# schdesign.net
KiCad netlist of a schematic drawn in EasyEDA
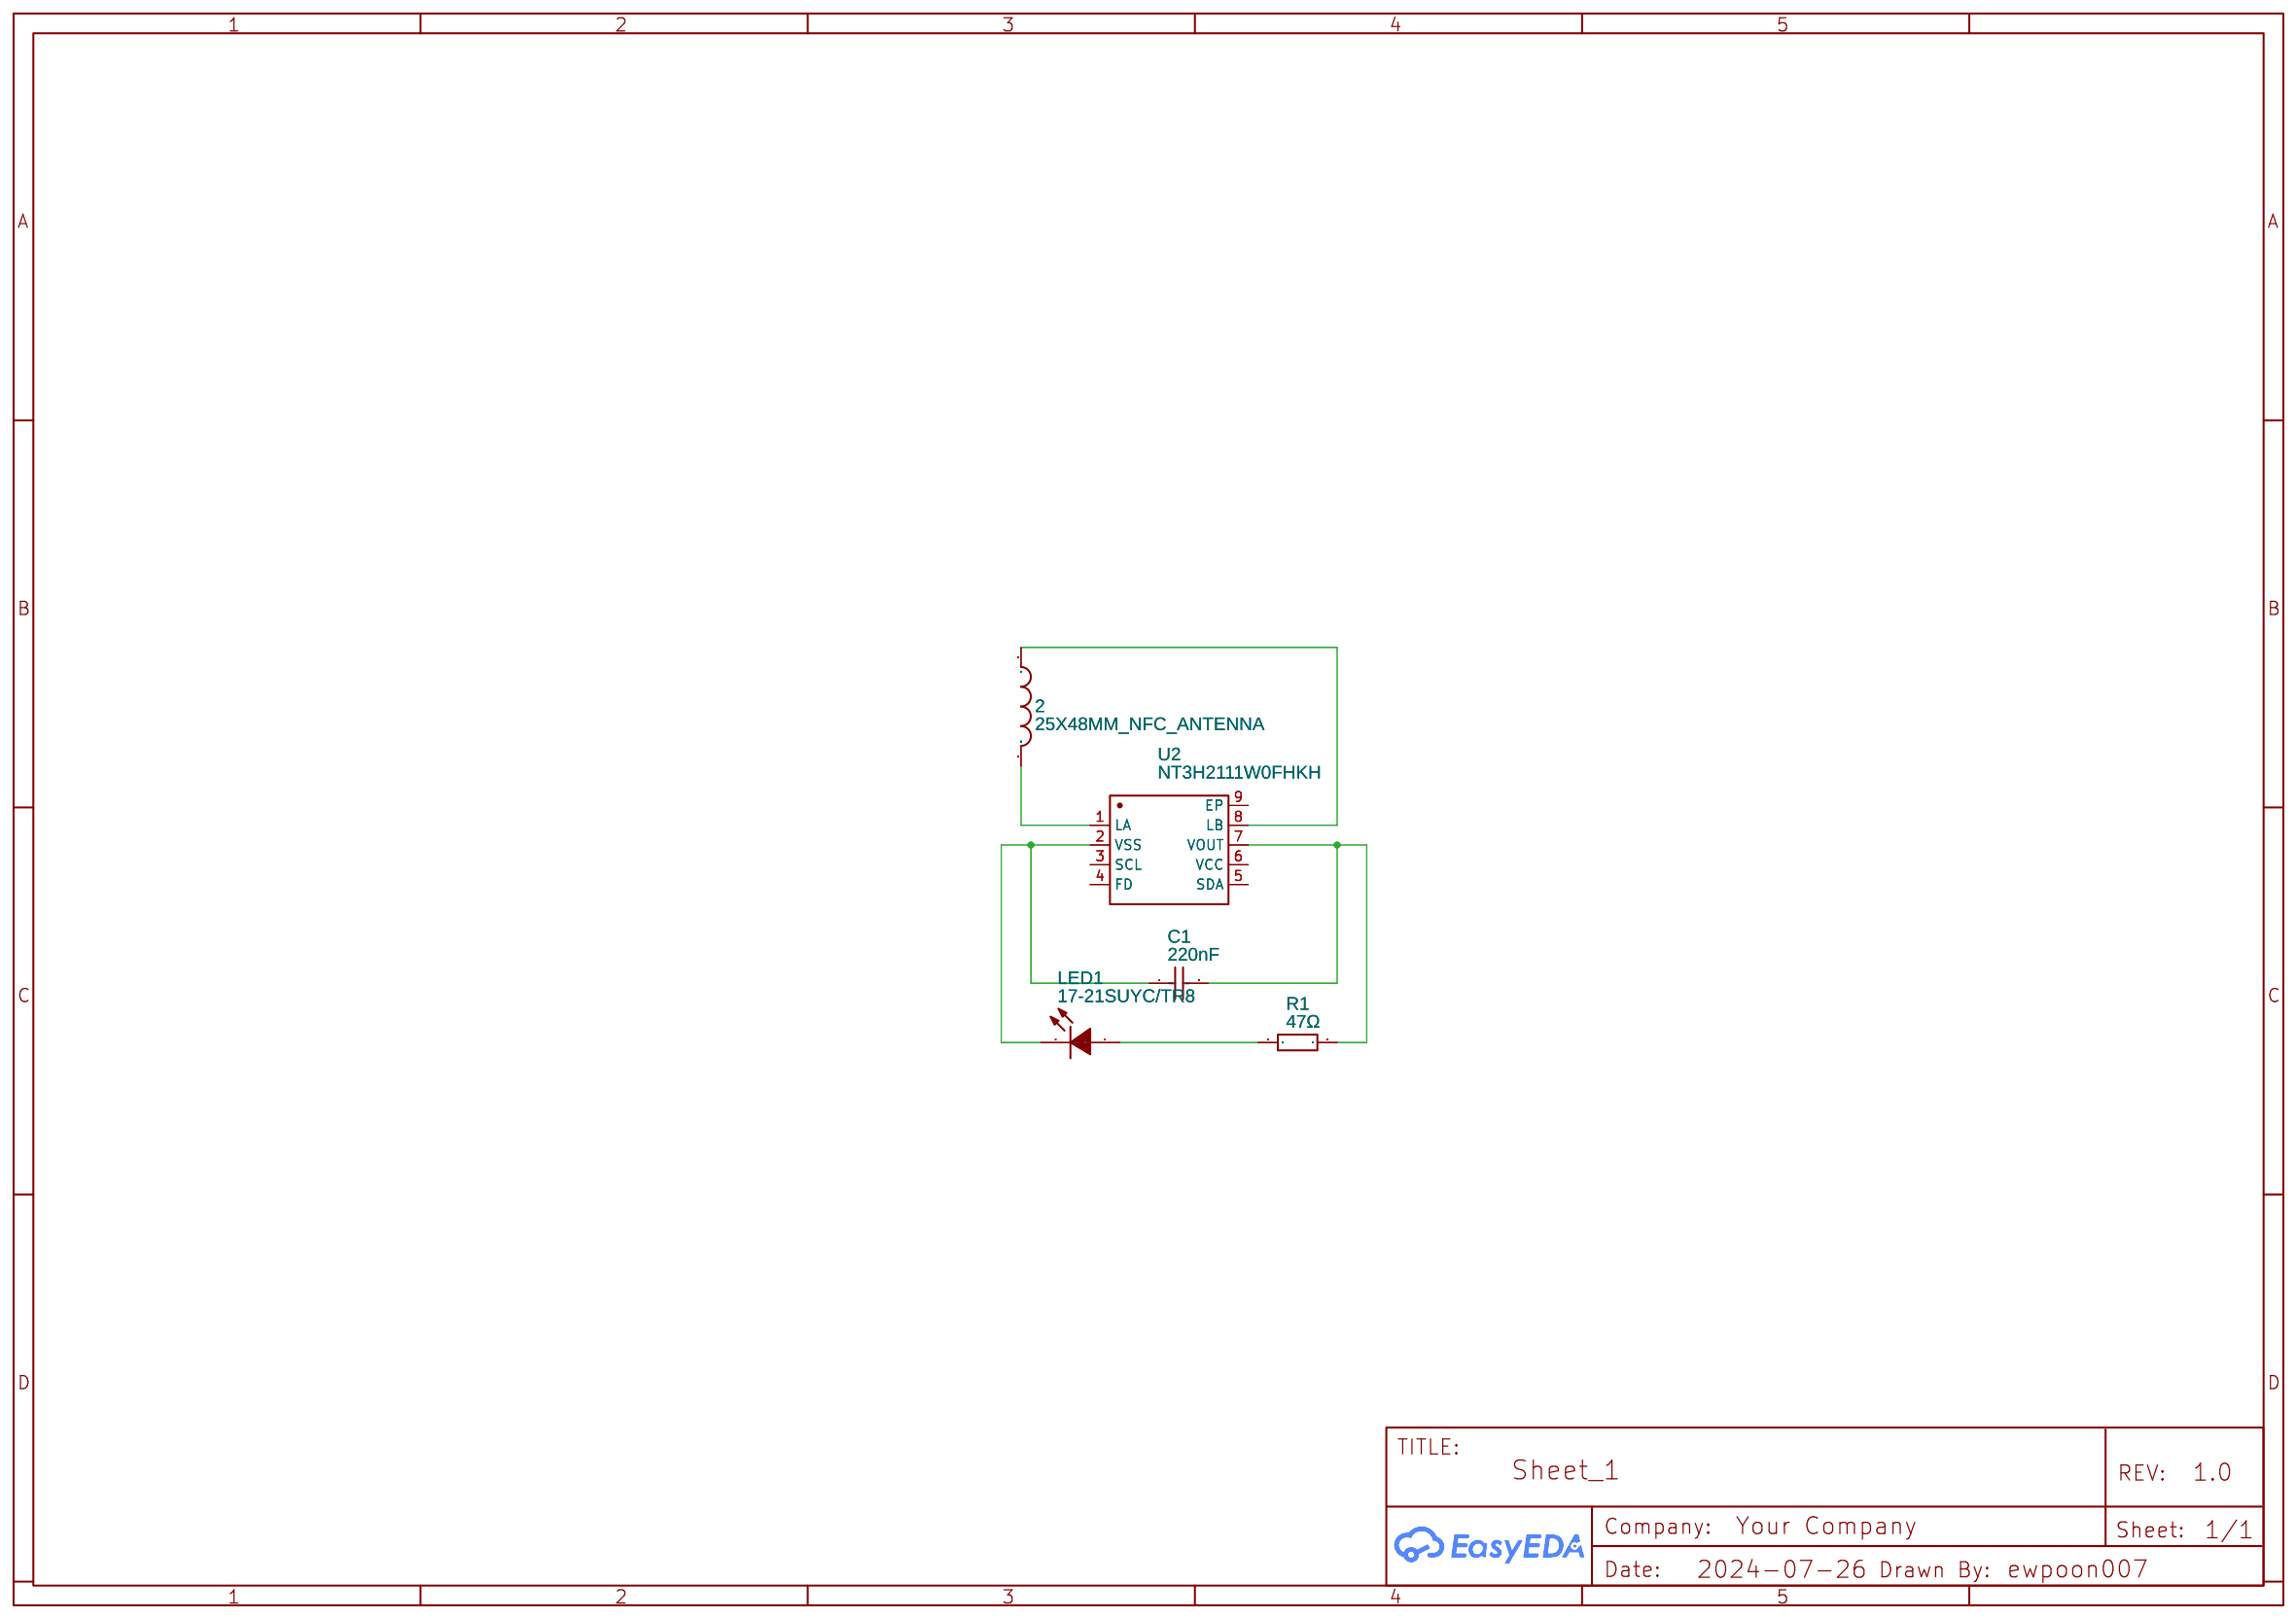
[diagram p0: schematic sheet]

(export (version "E")
  (design (tool "Eeschema 10.0.6"))
  (components
    (comp (ref "2") (value "25X48MM_NFC_ANTENNA") (libsource (lib "") (part "25X48MM_NFC_ANTENNA")))
    (comp (ref "C1")
      (value "220nF")
      (fields
        (field (name "Manufacturer Part") "CL10B224KA8NNNC")
        (field (name "Manufacturer") "SAMSUNG(三星)")
      )
      (libsource (lib "") (part "CL10B224KA8NNNC"))
    )
    (comp (ref "LED1")
      (value "17-21SUYC/TR8")
      (fields (field (name "Manufacturer Part") "KT-0805黄灯") (field (name "Manufacturer") "KENTO"))
      (libsource (lib "") (part "17-21SUYC/TR8"))
    )
    (comp (ref "R1")
      (value "47Ω")
      (fields
        (field (name "Manufacturer Part") "0603WAF470JT5E")
        (field (name "Manufacturer") "UNI-ROYAL(厚声)")
      )
      (libsource (lib "") (part "0603WAF470JT5E"))
    )
    (comp (ref "U2")
      (value "NT3H2111W0FHKH")
      (fields (field (name "Manufacturer") "NXP(恩智浦)"))
      (libsource (lib "") (part "NT3H2111W0FHKH"))
    )
  )
  (nets
    (net (code "1") (name "Net-(LED1-+)") (class "Default")
      (node (ref "LED1") (pin "1") (pinfunction "+_1") (pintype "unspecified"))
      (node (ref "R1") (pin "1") (pinfunction "1_1") (pintype "input"))
    )
    (net (code "2") (name "Net-(LED1--)") (class "Default")
      (node (ref "C1") (pin "1") (pinfunction "1_1") (pintype "input"))
      (node (ref "LED1") (pin "2") (pinfunction "-_2") (pintype "unspecified"))
      (node (ref "U2") (pin "2") (pinfunction "VSS_2") (pintype "unspecified"))
    )
    (net (code "3") (name "Net-(U2-LA)") (class "Default")
      (node (ref "2") (pin "P$2") (pinfunction "P$2_P$2") (pintype "bidirectional"))
      (node (ref "U2") (pin "1") (pinfunction "LA_1") (pintype "unspecified"))
    )
    (net (code "4") (name "Net-(U2-LB)") (class "Default")
      (node (ref "2") (pin "P$1") (pinfunction "P$1_P$1") (pintype "bidirectional"))
      (node (ref "U2") (pin "8") (pinfunction "LB_8") (pintype "unspecified"))
    )
    (net (code "5") (name "Net-(U2-VOUT)") (class "Default")
      (node (ref "C1") (pin "2") (pinfunction "2_2") (pintype "input"))
      (node (ref "R1") (pin "2") (pinfunction "2_2") (pintype "input"))
      (node (ref "U2") (pin "7") (pinfunction "VOUT_7") (pintype "unspecified"))
    )
    (net (code "6") (name "unconnected-(U2-EP-Pad9)") (class "Default")
      (node (ref "U2") (pin "9") (pinfunction "EP_9") (pintype "unspecified"))
    )
    (net (code "7") (name "unconnected-(U2-FD-Pad4)") (class "Default")
      (node (ref "U2") (pin "4") (pinfunction "FD_4") (pintype "unspecified"))
    )
    (net (code "8") (name "unconnected-(U2-SCL-Pad3)") (class "Default")
      (node (ref "U2") (pin "3") (pinfunction "SCL_3") (pintype "unspecified"))
    )
    (net (code "9") (name "unconnected-(U2-SDA-Pad5)") (class "Default")
      (node (ref "U2") (pin "5") (pinfunction "SDA_5") (pintype "unspecified"))
    )
    (net (code "10") (name "unconnected-(U2-VCC-Pad6)") (class "Default")
      (node (ref "U2") (pin "6") (pinfunction "VCC_6") (pintype "unspecified"))
    )
  )
)
